# Sheet1.net
KiCad netlist of a schematic drawn in Altium Designer
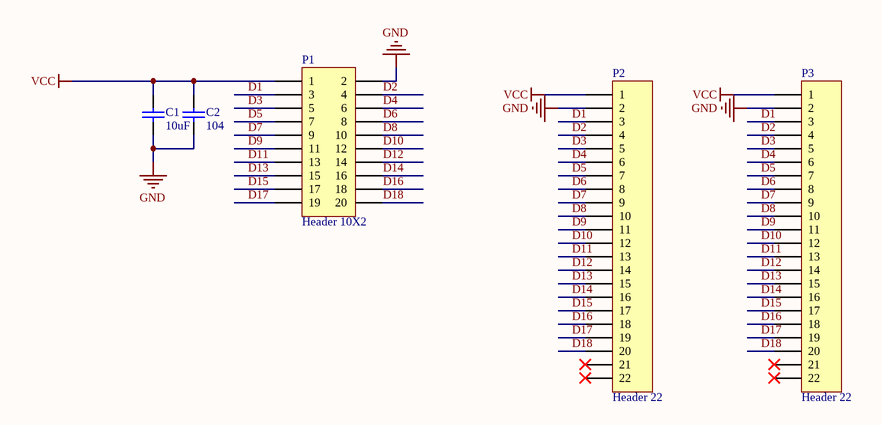
[diagram p0: Sheet1.SchDoc]

(export (version "E")
  (design (tool "Eeschema 10.0.6"))
  (components
    (comp (ref "C1")
      (value "10uF")
      (footprint "C0805")
      (description "Capacitor")
      (fields (field (name "Comment") "Cap") (field (name "PUBLISHER") "Altium Limited"))
      (libsource (lib "Miscellaneous Devices") (part "Cap"))
    )
    (comp (ref "C2")
      (value "104")
      (footprint "C0805")
      (description "Capacitor")
      (fields (field (name "Comment") "Cap") (field (name "PUBLISHER") "Altium Limited"))
      (libsource (lib "Miscellaneous Devices") (part "Cap"))
    )
    (comp (ref "P1")
      (value "Header 10X2")
      (footprint "HDR2X10")
      (description "Header, 10-Pin, Dual row")
      (fields (field (name "PUBLISHER") "Altium Limited"))
      (libsource (lib "Miscellaneous Connectors") (part "Header 10X2"))
    )
    (comp (ref "P2")
      (value "Header 22")
      (footprint "FPC20Pin")
      (description "Header, 22-Pin")
      (fields (field (name "PUBLISHER") "Altium Limited"))
      (libsource (lib "Miscellaneous Connectors") (part "Header 22"))
    )
    (comp (ref "P3")
      (value "Header 22")
      (footprint "FPC20Pin")
      (description "Header, 22-Pin")
      (fields (field (name "PUBLISHER") "Altium Limited"))
      (libsource (lib "Miscellaneous Connectors") (part "Header 22"))
    )
  )
  (nets
    (net (code "1") (name "/D1") (class "Default")
      (node (ref "P1") (pin "3") (pinfunction "3_3") (pintype "passive"))
      (node (ref "P2") (pin "3") (pinfunction "3_3") (pintype "passive"))
      (node (ref "P3") (pin "3") (pinfunction "3_3") (pintype "passive"))
    )
    (net (code "2") (name "/D2") (class "Default")
      (node (ref "P1") (pin "4") (pinfunction "4_4") (pintype "passive"))
      (node (ref "P2") (pin "4") (pinfunction "4_4") (pintype "passive"))
      (node (ref "P3") (pin "4") (pinfunction "4_4") (pintype "passive"))
    )
    (net (code "3") (name "/D3") (class "Default")
      (node (ref "P1") (pin "5") (pinfunction "5_5") (pintype "passive"))
      (node (ref "P2") (pin "5") (pinfunction "5_5") (pintype "passive"))
      (node (ref "P3") (pin "5") (pinfunction "5_5") (pintype "passive"))
    )
    (net (code "4") (name "/D4") (class "Default")
      (node (ref "P1") (pin "6") (pinfunction "6_6") (pintype "passive"))
      (node (ref "P2") (pin "6") (pinfunction "6_6") (pintype "passive"))
      (node (ref "P3") (pin "6") (pinfunction "6_6") (pintype "passive"))
    )
    (net (code "5") (name "/D5") (class "Default")
      (node (ref "P1") (pin "7") (pinfunction "7_7") (pintype "passive"))
      (node (ref "P2") (pin "7") (pinfunction "7_7") (pintype "passive"))
      (node (ref "P3") (pin "7") (pinfunction "7_7") (pintype "passive"))
    )
    (net (code "6") (name "/D6") (class "Default")
      (node (ref "P1") (pin "8") (pinfunction "8_8") (pintype "passive"))
      (node (ref "P2") (pin "8") (pinfunction "8_8") (pintype "passive"))
      (node (ref "P3") (pin "8") (pinfunction "8_8") (pintype "passive"))
    )
    (net (code "7") (name "/D7") (class "Default")
      (node (ref "P1") (pin "9") (pinfunction "9_9") (pintype "passive"))
      (node (ref "P2") (pin "9") (pinfunction "9_9") (pintype "passive"))
      (node (ref "P3") (pin "9") (pinfunction "9_9") (pintype "passive"))
    )
    (net (code "8") (name "/D8") (class "Default")
      (node (ref "P1") (pin "10") (pinfunction "10_10") (pintype "passive"))
      (node (ref "P2") (pin "10") (pinfunction "10_10") (pintype "passive"))
      (node (ref "P3") (pin "10") (pinfunction "10_10") (pintype "passive"))
    )
    (net (code "9") (name "/D9") (class "Default")
      (node (ref "P1") (pin "11") (pinfunction "11_11") (pintype "passive"))
      (node (ref "P2") (pin "11") (pinfunction "11_11") (pintype "passive"))
      (node (ref "P3") (pin "11") (pinfunction "11_11") (pintype "passive"))
    )
    (net (code "10") (name "/D10") (class "Default")
      (node (ref "P1") (pin "12") (pinfunction "12_12") (pintype "passive"))
      (node (ref "P2") (pin "12") (pinfunction "12_12") (pintype "passive"))
      (node (ref "P3") (pin "12") (pinfunction "12_12") (pintype "passive"))
    )
    (net (code "11") (name "/D11") (class "Default")
      (node (ref "P1") (pin "13") (pinfunction "13_13") (pintype "passive"))
      (node (ref "P2") (pin "13") (pinfunction "13_13") (pintype "passive"))
      (node (ref "P3") (pin "13") (pinfunction "13_13") (pintype "passive"))
    )
    (net (code "12") (name "/D12") (class "Default")
      (node (ref "P1") (pin "14") (pinfunction "14_14") (pintype "passive"))
      (node (ref "P2") (pin "14") (pinfunction "14_14") (pintype "passive"))
      (node (ref "P3") (pin "14") (pinfunction "14_14") (pintype "passive"))
    )
    (net (code "13") (name "/D13") (class "Default")
      (node (ref "P1") (pin "15") (pinfunction "15_15") (pintype "passive"))
      (node (ref "P2") (pin "15") (pinfunction "15_15") (pintype "passive"))
      (node (ref "P3") (pin "15") (pinfunction "15_15") (pintype "passive"))
    )
    (net (code "14") (name "/D14") (class "Default")
      (node (ref "P1") (pin "16") (pinfunction "16_16") (pintype "passive"))
      (node (ref "P2") (pin "16") (pinfunction "16_16") (pintype "passive"))
      (node (ref "P3") (pin "16") (pinfunction "16_16") (pintype "passive"))
    )
    (net (code "15") (name "/D15") (class "Default")
      (node (ref "P1") (pin "17") (pinfunction "17_17") (pintype "passive"))
      (node (ref "P2") (pin "17") (pinfunction "17_17") (pintype "passive"))
      (node (ref "P3") (pin "17") (pinfunction "17_17") (pintype "passive"))
    )
    (net (code "16") (name "/D16") (class "Default")
      (node (ref "P1") (pin "18") (pinfunction "18_18") (pintype "passive"))
      (node (ref "P2") (pin "18") (pinfunction "18_18") (pintype "passive"))
      (node (ref "P3") (pin "18") (pinfunction "18_18") (pintype "passive"))
    )
    (net (code "17") (name "/D17") (class "Default")
      (node (ref "P1") (pin "19") (pinfunction "19_19") (pintype "passive"))
      (node (ref "P2") (pin "19") (pinfunction "19_19") (pintype "passive"))
      (node (ref "P3") (pin "19") (pinfunction "19_19") (pintype "passive"))
    )
    (net (code "18") (name "/D18") (class "Default")
      (node (ref "P1") (pin "20") (pinfunction "20_20") (pintype "passive"))
      (node (ref "P2") (pin "20") (pinfunction "20_20") (pintype "passive"))
      (node (ref "P3") (pin "20") (pinfunction "20_20") (pintype "passive"))
    )
    (net (code "19") (name "GND") (class "Default")
      (node (ref "C1") (pin "1") (pinfunction "1_1") (pintype "passive"))
      (node (ref "C2") (pin "1") (pinfunction "1_1") (pintype "passive"))
      (node (ref "P1") (pin "2") (pinfunction "2_2") (pintype "passive"))
      (node (ref "P2") (pin "2") (pinfunction "2_2") (pintype "passive"))
      (node (ref "P3") (pin "2") (pinfunction "2_2") (pintype "passive"))
    )
    (net (code "20") (name "VCC") (class "Default")
      (node (ref "C1") (pin "2") (pinfunction "2_2") (pintype "passive"))
      (node (ref "C2") (pin "2") (pinfunction "2_2") (pintype "passive"))
      (node (ref "P1") (pin "1") (pinfunction "1_1") (pintype "passive"))
      (node (ref "P2") (pin "1") (pinfunction "1_1") (pintype "passive"))
      (node (ref "P3") (pin "1") (pinfunction "1_1") (pintype "passive"))
    )
    (net (code "21") (name "unconnected-(P2-Pad21)") (class "Default")
      (node (ref "P2") (pin "21") (pinfunction "21_21") (pintype "passive+no_connect"))
    )
    (net (code "22") (name "unconnected-(P2-Pad22)") (class "Default")
      (node (ref "P2") (pin "22") (pinfunction "22_22") (pintype "passive+no_connect"))
    )
    (net (code "23") (name "unconnected-(P3-Pad21)") (class "Default")
      (node (ref "P3") (pin "21") (pinfunction "21_21") (pintype "passive+no_connect"))
    )
    (net (code "24") (name "unconnected-(P3-Pad22)") (class "Default")
      (node (ref "P3") (pin "22") (pinfunction "22_22") (pintype "passive+no_connect"))
    )
  )
)
